# jarvis_mini.net
KiCad netlist of a schematic drawn in Altium Designer
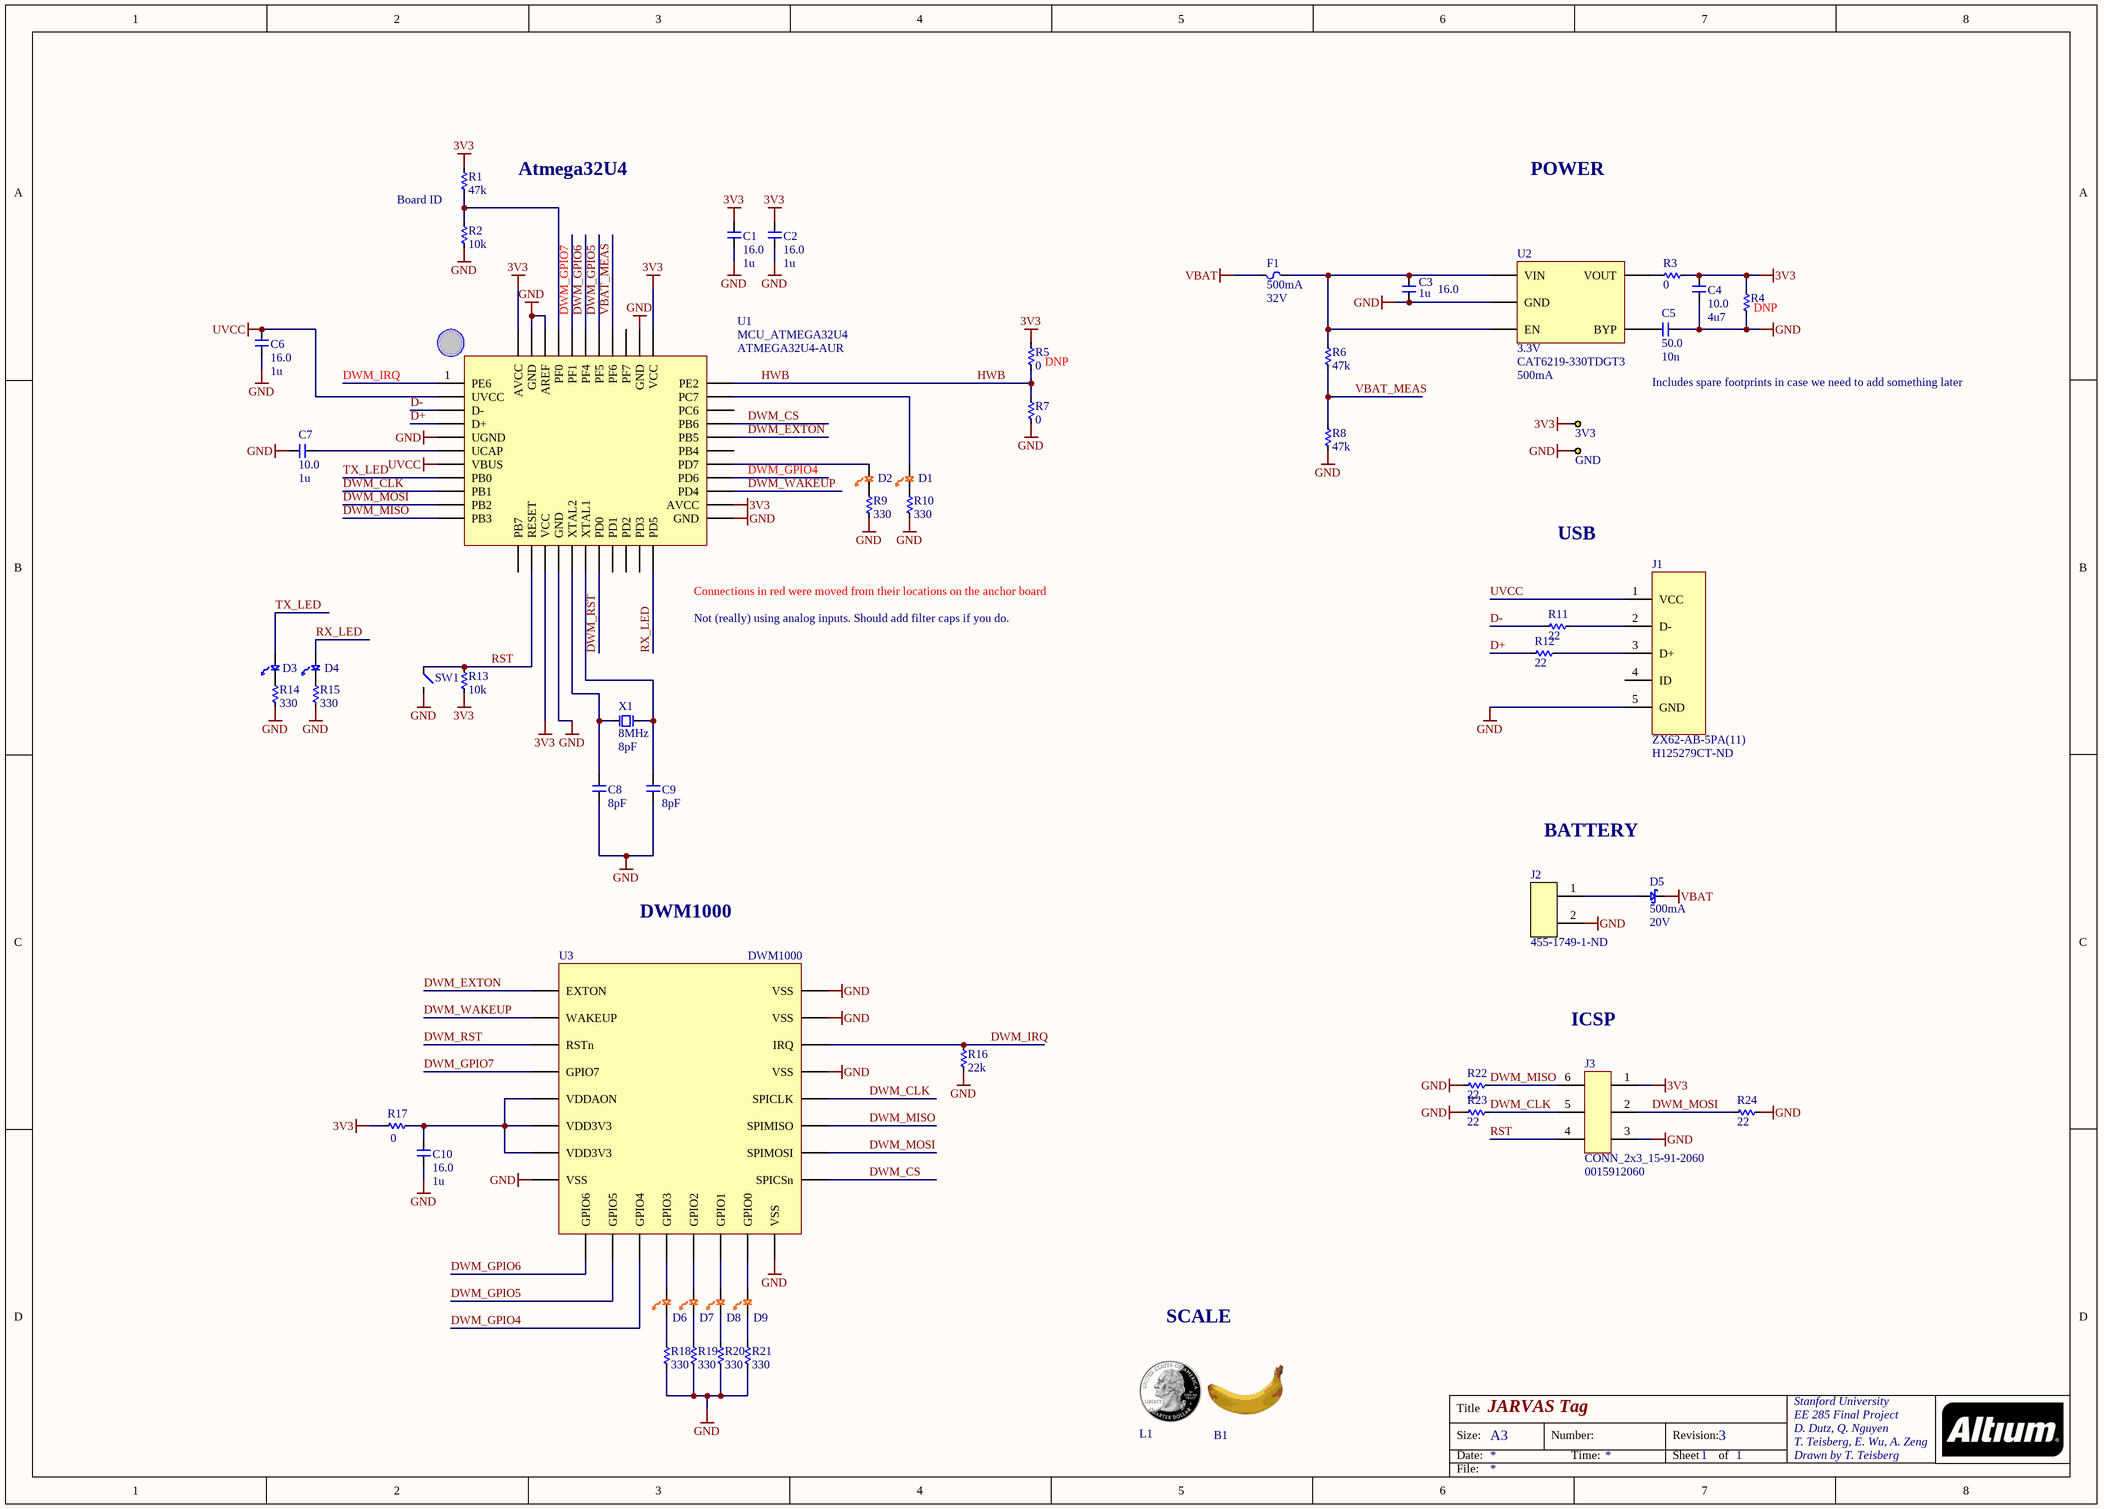
[diagram p0: jarvis_mini.SchDoc]

(export (version "E")
  (design (tool "Eeschema 10.0.6"))
  (components
    (comp (ref "3V3")
      (value "TEST_KEYSTONE5015")
      (footprint "TP_KEYSTONE_5015")
      (description "PC TEST POINT MINIATURE SMT")
      (fields
        (field (name "MANUFACTURER") "Keystone Electronics")
        (field (name "MANUFACTURER PART NUMBER") "5015")
      )
      (libsource (lib "SSI") (part "TEST_KEYSTONE5015"))
    )
    (comp (ref "B1")
      (value "Banananannaa!")
      (footprint "BANANA_OPEN")
      (description "Banana for scale")
      (fields (field (name "MANUFACTURER") "Dole") (field (name "MANUFACTURER PART NUMBER") "B-0000001"))
      (libsource (lib "SSI") (part "BANANA"))
    )
    (comp (ref "C1")
      (value "__template_cap")
      (footprint "C0603")
      (fields
        (field (name "VOLTAGE") "16.0")
        (field (name "HUMAN_VALUE") "1u")
        (field (name "TOLERANCE") "10%")
      )
      (libsource (lib "sscp") (part "__template_cap"))
    )
    (comp (ref "C2")
      (value "__template_cap")
      (footprint "C0603")
      (fields
        (field (name "VOLTAGE") "16.0")
        (field (name "HUMAN_VALUE") "1u")
        (field (name "TOLERANCE") "10%")
      )
      (libsource (lib "sscp") (part "__template_cap"))
    )
    (comp (ref "C3")
      (value "__template_cap")
      (footprint "C0603")
      (fields
        (field (name "VOLTAGE") "16.0")
        (field (name "HUMAN_VALUE") "1u")
        (field (name "TOLERANCE") "10%")
      )
      (libsource (lib "sscp") (part "__template_cap"))
    )
    (comp (ref "C4")
      (value "__template_cap")
      (footprint "C0603")
      (fields
        (field (name "VOLTAGE") "10.0")
        (field (name "HUMAN_VALUE") "4u7")
        (field (name "TOLERANCE") "10%")
      )
      (libsource (lib "sscp") (part "__template_cap"))
    )
    (comp (ref "C5")
      (value "__template_cap")
      (footprint "C0603")
      (fields
        (field (name "VOLTAGE") "50.0")
        (field (name "HUMAN_VALUE") "10n")
        (field (name "TOLERANCE") "5%")
      )
      (libsource (lib "sscp") (part "__template_cap"))
    )
    (comp (ref "C6")
      (value "__template_cap")
      (footprint "C0603")
      (fields
        (field (name "VOLTAGE") "16.0")
        (field (name "HUMAN_VALUE") "1u")
        (field (name "TOLERANCE") "10%")
      )
      (libsource (lib "sscp") (part "__template_cap"))
    )
    (comp (ref "C7")
      (value "__template_cap")
      (footprint "C0603")
      (fields
        (field (name "VOLTAGE") "10.0")
        (field (name "HUMAN_VALUE") "1u")
        (field (name "TOLERANCE") "10%")
      )
      (libsource (lib "sscp") (part "__template_cap"))
    )
    (comp (ref "C8")
      (value "CAP_CER_8PF_100V")
      (footprint "C0603")
      (fields
        (field (name "MANUFACTURER") "AVX Corporation")
        (field (name "MANUFACTURER PART NUMBER") "06031A8R0CAT2A")
        (field (name "TOLERANCE") "±0.25pF")
        (field (name "CAPACITANCE") "8pF")
      )
      (libsource (lib "SSI") (part "CAP_CER_8PF_100V"))
    )
    (comp (ref "C9")
      (value "CAP_CER_8PF_100V")
      (footprint "C0603")
      (fields
        (field (name "MANUFACTURER") "AVX Corporation")
        (field (name "MANUFACTURER PART NUMBER") "06031A8R0CAT2A")
        (field (name "TOLERANCE") "±0.25pF")
        (field (name "CAPACITANCE") "8pF")
      )
      (libsource (lib "SSI") (part "CAP_CER_8PF_100V"))
    )
    (comp (ref "C10")
      (value "__template_cap")
      (footprint "C0603")
      (fields
        (field (name "VOLTAGE") "16.0")
        (field (name "HUMAN_VALUE") "1u")
        (field (name "TOLERANCE") "10%")
      )
      (libsource (lib "sscp") (part "__template_cap"))
    )
    (comp (ref "D1")
      (value "LED")
      (footprint "LED_0603P_ORANGE")
      (description "Orange 605nm LED Indication - Discrete 2V 0603 (1608 Metric)")
      (fields
        (field (name "MANUFACTURER") "Lite-On Inc.")
        (field (name "MANUFACTURER PART NUMBER") "LTST-C190KFKT")
      )
      (libsource (lib "SSI") (part "LED_LTST-C190KFKT_ORANGE"))
    )
    (comp (ref "D2")
      (value "LED")
      (footprint "LED_0603P_ORANGE")
      (description "Orange 605nm LED Indication - Discrete 2V 0603 (1608 Metric)")
      (fields
        (field (name "MANUFACTURER") "Lite-On Inc.")
        (field (name "MANUFACTURER PART NUMBER") "LTST-C190KFKT")
      )
      (libsource (lib "SSI") (part "LED_LTST-C190KFKT_ORANGE"))
    )
    (comp (ref "D3")
      (value "LED_LBQ39G_BLUE")
      (footprint "LED_0603P_BLUE")
      (description "Blue 470nm LED Indication - Discrete 2.85V 0603 (1608 Metric)")
      (fields
        (field (name "MANUFACTURER") "OSRAM Opto Semiconductors Inc.")
        (field (name "MANUFACTURER PART NUMBER") "LB Q39G-L2OO-35-1")
      )
      (libsource (lib "SSI") (part "LED_LBQ39G_BLUE"))
    )
    (comp (ref "D4")
      (value "LED_LBQ39G_BLUE")
      (footprint "LED_0603P_BLUE")
      (description "Blue 470nm LED Indication - Discrete 2.85V 0603 (1608 Metric)")
      (fields
        (field (name "MANUFACTURER") "OSRAM Opto Semiconductors Inc.")
        (field (name "MANUFACTURER PART NUMBER") "LB Q39G-L2OO-35-1")
      )
      (libsource (lib "SSI") (part "LED_LBQ39G_BLUE"))
    )
    (comp (ref "D5")
      (value "SCHOTTKY_MBR0520L")
      (footprint "SOD123")
      (description "DIODE SCHOTTKY 0.5A 20V SOD-123")
      (fields
        (field (name "MANUFACTURER") "Fairchild Semiconductor")
        (field (name "MANUFACTURER PART NUMBER") "MBR0520L")
        (field (name "CURRENT - AVERAGE RECTIFIED (IO)") "500mA")
        (field (name "VOLTAGE - DC REVERSE (VR) (MAX)") "20V")
      )
      (libsource (lib "SSI") (part "SCHOTTKY_MBR0520L"))
    )
    (comp (ref "D6")
      (value "LED")
      (footprint "LED0603")
      (description "Orange 605nm LED Indication - Discrete 2V 0603 (1608 Metric)")
      (fields
        (field (name "MANUFACTURER") "Lite-On Inc.")
        (field (name "MANUFACTURER PART NUMBER") "LTST-C190KFKT")
      )
      (libsource (lib "ee285") (part "LED_LTST-C190KFKT_ORANGE"))
    )
    (comp (ref "D7")
      (value "LED")
      (footprint "LED0603")
      (description "Orange 605nm LED Indication - Discrete 2V 0603 (1608 Metric)")
      (fields
        (field (name "MANUFACTURER") "Lite-On Inc.")
        (field (name "MANUFACTURER PART NUMBER") "LTST-C190KFKT")
      )
      (libsource (lib "ee285") (part "LED_LTST-C190KFKT_ORANGE"))
    )
    (comp (ref "D8")
      (value "LED")
      (footprint "LED0603")
      (description "Orange 605nm LED Indication - Discrete 2V 0603 (1608 Metric)")
      (fields
        (field (name "MANUFACTURER") "Lite-On Inc.")
        (field (name "MANUFACTURER PART NUMBER") "LTST-C190KFKT")
      )
      (libsource (lib "ee285") (part "LED_LTST-C190KFKT_ORANGE"))
    )
    (comp (ref "D9")
      (value "LED")
      (footprint "LED0603")
      (description "Orange 605nm LED Indication - Discrete 2V 0603 (1608 Metric)")
      (fields
        (field (name "MANUFACTURER") "Lite-On Inc.")
        (field (name "MANUFACTURER PART NUMBER") "LTST-C190KFKT")
      )
      (libsource (lib "ee285") (part "LED_LTST-C190KFKT_ORANGE"))
    )
    (comp (ref "F1")
      (value "FAST_MFU0805.50CT-ND")
      (footprint "R0805")
      (description "FUSE .50A 0805 VFAST SMD")
      (fields
        (field (name "MANUFACTURER") "Vishay Beyschlag")
        (field (name "MANUFACTURER PART NUMBER") "MFU0805FF00500P100")
        (field (name "CURRENT RATING") "500mA")
        (field (name "VOLTAGE RATING - DC") "32V")
      )
      (libsource (lib "SSI") (part "FAST_MFU0805.50CT-ND"))
    )
    (comp (ref "GND")
      (value "TEST_KEYSTONE5015")
      (footprint "TP_KEYSTONE_5015")
      (description "PC TEST POINT MINIATURE SMT")
      (fields
        (field (name "MANUFACTURER") "Keystone Electronics")
        (field (name "MANUFACTURER PART NUMBER") "5015")
      )
      (libsource (lib "SSI") (part "TEST_KEYSTONE5015"))
    )
    (comp (ref "J1")
      (value "CONN_USB_MICROAB_SMD_R/A")
      (footprint "HIROSE_ZX62-AB-5PA")
      (description "CONN RCPT MICRO USB AB SMD R/A")
      (fields
        (field (name "MANUFACTURER") "Hirose Electric Co Ltd")
        (field (name "MANUFACTURER PART NUMBER") "ZX62-AB-5PA(11)")
        (field (name "SUPPLIER PART NUMBER 1") "H125279CT-ND")
      )
      (libsource (lib "SSI") (part "CONN_USB_MICROAB_SMD_R/A"))
    )
    (comp (ref "J2")
      (value "CONN JST 2POS SMD")
      (footprint "CONN_JST_PH_SM4_2PIN_RA")
      (description "CONN HEADER PH SIDE 2POS 2MM SMD")
      (fields
        (field (name "MANUFACTURER") "JST Sales America Inc.")
        (field (name "MANUFACTURER PART NUMBER") "S2B-PH-SM4-TB(LF)(SN)")
        (field (name "SUPPLIER PART NUMBER 1") "455-1749-1-ND")
      )
      (libsource (lib "SSI") (part "CONN_JST_2_PH"))
    )
    (comp (ref "J3")
      (value "CONN_2x3_15-91-2060")
      (footprint "MOLEX_15-91-2060")
      (description "CONN HEADER 6POS .100\" VERT TIN")
      (fields
        (field (name "MANUFACTURER") "Molex Inc")
        (field (name "MANUFACTURER PART NUMBER") "0015912060")
      )
      (libsource (lib "SSI") (part "CONN_2x3_15-91-2060"))
    )
    (comp (ref "L1")
      (value "QUARTER")
      (footprint "Quarter")
      (description "Quarter for scale")
      (libsource (lib "SSI") (part "QUARTER"))
    )
    (comp (ref "R1")
      (value "47k")
      (footprint "R0603")
      (description "RES SMD 47K OHM 1% 1/10W 0603")
      (fields
        (field (name "MANUFACTURER PART NUMBER") "CRCW060347K0FKEA")
        (field (name "MANUFACTURER") "Vishay Dale")
      )
      (libsource (lib "resistor") (part "__template_resistor"))
    )
    (comp (ref "R2")
      (value "10k")
      (footprint "R0603")
      (description "RES SMD 10K OHM 1% 1/10W 0603")
      (fields
        (field (name "MANUFACTURER PART NUMBER") "CRCW060310K0FKEA")
        (field (name "MANUFACTURER") "Vishay Dale")
      )
      (libsource (lib "resistor") (part "__template_resistor"))
    )
    (comp (ref "R3")
      (value "0")
      (footprint "R0603")
      (description "RES SMD 0.0 OHM")
      (fields
        (field (name "MANUFACTURER PART NUMBER") "CRCW06030000Z0EA")
        (field (name "MANUFACTURER") "Vishay Dale")
      )
      (libsource (lib "resistor") (part "__template_resistor"))
    )
    (comp (ref "R4")
      (value "__template_resistor")
      (footprint "R0603")
      (description "RES SMD 0.0 OHM")
      (fields
        (field (name "MANUFACTURER PART NUMBER") "CRCW06030000Z0EA")
        (field (name "MANUFACTURER") "Vishay Dale")
        (field (name "DNP") "DNP")
      )
      (libsource (lib "resistor") (part "__template_resistor"))
    )
    (comp (ref "R5")
      (value "0")
      (footprint "R0603")
      (description "RES SMD 0.0 OHM")
      (fields
        (field (name "MANUFACTURER PART NUMBER") "CRCW06030000Z0EA")
        (field (name "MANUFACTURER") "Vishay Dale")
        (field (name "DNP") "DNP")
      )
      (libsource (lib "resistor") (part "__template_resistor"))
    )
    (comp (ref "R6")
      (value "47k")
      (footprint "R0603")
      (description "RES SMD 47K OHM 1% 1/10W 0603")
      (fields
        (field (name "MANUFACTURER PART NUMBER") "CRCW060347K0FKEA")
        (field (name "MANUFACTURER") "Vishay Dale")
      )
      (libsource (lib "resistor") (part "__template_resistor"))
    )
    (comp (ref "R7")
      (value "0")
      (footprint "R0603")
      (description "RES SMD 0.0 OHM")
      (fields
        (field (name "MANUFACTURER PART NUMBER") "CRCW06030000Z0EA")
        (field (name "MANUFACTURER") "Vishay Dale")
      )
      (libsource (lib "resistor") (part "__template_resistor"))
    )
    (comp (ref "R8")
      (value "47k")
      (footprint "R0603")
      (description "RES SMD 47K OHM 1% 1/10W 0603")
      (fields
        (field (name "MANUFACTURER PART NUMBER") "CRCW060347K0FKEA")
        (field (name "MANUFACTURER") "Vishay Dale")
      )
      (libsource (lib "resistor") (part "__template_resistor"))
    )
    (comp (ref "R9")
      (value "330")
      (footprint "R0603")
      (description "RES SMD 330 OHM 1% 1/10W 0603")
      (fields
        (field (name "MANUFACTURER PART NUMBER") "CRCW0603330RFKEA")
        (field (name "MANUFACTURER") "Vishay Dale")
      )
      (libsource (lib "resistor") (part "__template_resistor"))
    )
    (comp (ref "R10")
      (value "330")
      (footprint "R0603")
      (description "RES SMD 330 OHM 1% 1/10W 0603")
      (fields
        (field (name "MANUFACTURER PART NUMBER") "CRCW0603330RFKEA")
        (field (name "MANUFACTURER") "Vishay Dale")
      )
      (libsource (lib "resistor") (part "__template_resistor"))
    )
    (comp (ref "R11")
      (value "22")
      (footprint "R0603")
      (description "RES SMD 22 OHM 1% 1/10W 0603")
      (fields
        (field (name "MANUFACTURER PART NUMBER") "CRCW060322R0FKEA")
        (field (name "MANUFACTURER") "Vishay Dale")
      )
      (libsource (lib "resistor") (part "__template_resistor"))
    )
    (comp (ref "R12")
      (value "22")
      (footprint "R0603")
      (description "RES SMD 22 OHM 1% 1/10W 0603")
      (fields
        (field (name "MANUFACTURER PART NUMBER") "CRCW060322R0FKEA")
        (field (name "MANUFACTURER") "Vishay Dale")
      )
      (libsource (lib "resistor") (part "__template_resistor"))
    )
    (comp (ref "R13")
      (value "10k")
      (footprint "R0603")
      (description "RES SMD 10K OHM 1% 1/10W 0603")
      (fields
        (field (name "MANUFACTURER PART NUMBER") "CRCW060310K0FKEA")
        (field (name "MANUFACTURER") "Vishay Dale")
      )
      (libsource (lib "resistor") (part "__template_resistor"))
    )
    (comp (ref "R14")
      (value "330")
      (footprint "R0603")
      (description "RES SMD 330 OHM 1% 1/10W 0603")
      (fields
        (field (name "MANUFACTURER PART NUMBER") "CRCW0603330RFKEA")
        (field (name "MANUFACTURER") "Vishay Dale")
      )
      (libsource (lib "resistor") (part "__template_resistor"))
    )
    (comp (ref "R15")
      (value "330")
      (footprint "R0603")
      (description "RES SMD 330 OHM 1% 1/10W 0603")
      (fields
        (field (name "MANUFACTURER PART NUMBER") "CRCW0603330RFKEA")
        (field (name "MANUFACTURER") "Vishay Dale")
      )
      (libsource (lib "resistor") (part "__template_resistor"))
    )
    (comp (ref "R16")
      (value "22k")
      (footprint "R0603")
      (description "RES SMD 22K OHM 1% 1/10W 0603")
      (fields
        (field (name "MANUFACTURER PART NUMBER") "CRCW060322K0FKEA")
        (field (name "MANUFACTURER") "Vishay Dale")
      )
      (libsource (lib "resistor") (part "__template_resistor"))
    )
    (comp (ref "R17")
      (value "__template_resistor")
      (footprint "R0603")
      (description "RES SMD 0.0 OHM")
      (fields
        (field (name "MANUFACTURER PART NUMBER") "CRCW06030000Z0EA")
        (field (name "RESISTANCE (MACHINE READABLE)") "0")
        (field (name "MANUFACTURER") "Vishay Dale")
      )
      (libsource (lib "resistor") (part "__template_resistor"))
    )
    (comp (ref "R18")
      (value "330")
      (footprint "R0603")
      (description "RES SMD 330 OHM 1% 1/10W 0603")
      (fields
        (field (name "MANUFACTURER PART NUMBER") "CRCW0603330RFKEA")
        (field (name "MANUFACTURER") "Vishay Dale")
      )
      (libsource (lib "resistor") (part "__template_resistor"))
    )
    (comp (ref "R19")
      (value "330")
      (footprint "R0603")
      (description "RES SMD 330 OHM 1% 1/10W 0603")
      (fields
        (field (name "MANUFACTURER PART NUMBER") "CRCW0603330RFKEA")
        (field (name "MANUFACTURER") "Vishay Dale")
      )
      (libsource (lib "resistor") (part "__template_resistor"))
    )
    (comp (ref "R20")
      (value "330")
      (footprint "R0603")
      (description "RES SMD 330 OHM 1% 1/10W 0603")
      (fields
        (field (name "MANUFACTURER PART NUMBER") "CRCW0603330RFKEA")
        (field (name "MANUFACTURER") "Vishay Dale")
      )
      (libsource (lib "resistor") (part "__template_resistor"))
    )
    (comp (ref "R21")
      (value "330")
      (footprint "R0603")
      (description "RES SMD 330 OHM 1% 1/10W 0603")
      (fields
        (field (name "MANUFACTURER PART NUMBER") "CRCW0603330RFKEA")
        (field (name "MANUFACTURER") "Vishay Dale")
      )
      (libsource (lib "resistor") (part "__template_resistor"))
    )
    (comp (ref "R22")
      (value "22")
      (footprint "R0603")
      (description "RES SMD 22 OHM 1% 1/10W 0603")
      (fields
        (field (name "MANUFACTURER PART NUMBER") "CRCW060322R0FKEA")
        (field (name "MANUFACTURER") "Vishay Dale")
      )
      (libsource (lib "resistor") (part "__template_resistor"))
    )
    (comp (ref "R23")
      (value "22")
      (footprint "R0603")
      (description "RES SMD 22 OHM 1% 1/10W 0603")
      (fields
        (field (name "MANUFACTURER PART NUMBER") "CRCW060322R0FKEA")
        (field (name "MANUFACTURER") "Vishay Dale")
      )
      (libsource (lib "resistor") (part "__template_resistor"))
    )
    (comp (ref "R24")
      (value "22")
      (footprint "R0603")
      (description "RES SMD 22 OHM 1% 1/10W 0603")
      (fields
        (field (name "MANUFACTURER PART NUMBER") "CRCW060322R0FKEA")
        (field (name "MANUFACTURER") "Vishay Dale")
      )
      (libsource (lib "resistor") (part "__template_resistor"))
    )
    (comp (ref "SW1")
      (value "SWITCH_SPST-NO")
      (footprint "SWITCH_B3U-1000P")
      (description "SWITCH TACTILE SPST-NO 0.05A 12V")
      (fields
        (field (name "MANUFACTURER") "Omron Electronics Inc-EMC Div")
        (field (name "MANUFACTURER PART NUMBER") "B3U-1000P")
      )
      (libsource (lib "SSI") (part "SWITCH_SPST-NO"))
    )
    (comp (ref "U1")
      (value "MCU_ATMEGA32U4")
      (footprint "44TQFP10")
      (description "IC MCU 8BIT 32KB FLASH 44TQFP")
      (fields
        (field (name "MANUFACTURER") "Atmel")
        (field (name "MANUFACTURER PART NUMBER") "ATMEGA32U4-AUR")
      )
      (libsource (lib "SSI") (part "MCU_ATMEGA32U4"))
    )
    (comp (ref "U2")
      (value "3.3V LDO")
      (footprint "TSOT-23-5")
      (description "Linear Voltage Regulator IC Positive Fixed 1 Output 3.3V 500mA TSOT-23-5")
      (fields
        (field (name "MANUFACTURER") "ON Semiconductor")
        (field (name "VOLTAGE - OUTPUT") "3.3V")
        (field (name "MANUFACTURER PART NUMBER") "CAT6219-330TDGT3")
        (field (name "CURRENT - OUTPUT") "500mA")
      )
      (libsource (lib "ee285") (part "LDO_CAT6219_3V3"))
    )
    (comp (ref "U3")
      (value "DWM1000")
      (footprint "DW1000")
      (fields (field (name "MANUFACTURER") "Decawave Limited"))
      (libsource (lib "ee285") (part "DWM1000"))
    )
    (comp (ref "X1")
      (value "XTAL_NX5032GA")
      (footprint "XTAL_NDK_NX5032")
      (description "CRYSTAL 8.00 MHZ 8PF SMD")
      (fields
        (field (name "MANUFACTURER") "NDK")
        (field (name "MANUFACTURER PART NUMBER") "NX5032GA 8MHZ AT-W")
        (field (name "FREQUENCY") "8MHz")
        (field (name "LOAD CAPACITANCE") "8pF")
      )
      (libsource (lib "SSI") (part "XTAL_NX5032GA"))
    )
  )
  (nets
    (net (code "1") (name "/D+") (class "Default")
      (node (ref "R12") (pin "1") (pintype "passive"))
      (node (ref "U1") (pin "4") (pinfunction "D+_4") (pintype "passive"))
    )
    (net (code "2") (name "/D-") (class "Default")
      (node (ref "R11") (pin "1") (pintype "passive"))
      (node (ref "U1") (pin "3") (pinfunction "D-_3") (pintype "passive"))
    )
    (net (code "3") (name "/DWM_CLK") (class "Default")
      (node (ref "J3") (pin "5") (pintype "passive"))
      (node (ref "R23") (pin "2") (pintype "passive"))
      (node (ref "U1") (pin "9") (pinfunction "PB1_9") (pintype "passive"))
      (node (ref "U3") (pin "20") (pinfunction "SPICLK_20") (pintype "passive"))
    )
    (net (code "4") (name "/DWM_CS") (class "Default")
      (node (ref "U1") (pin "30") (pinfunction "PB6_30") (pintype "passive"))
      (node (ref "U3") (pin "17") (pinfunction "SPICSn_17") (pintype "passive"))
    )
    (net (code "5") (name "/DWM_EXTON") (class "Default")
      (node (ref "U1") (pin "29") (pinfunction "PB5_29") (pintype "passive"))
      (node (ref "U3") (pin "1") (pinfunction "EXTON_1") (pintype "passive"))
    )
    (net (code "6") (name "/DWM_GPIO4") (class "Default")
      (node (ref "U1") (pin "26") (pinfunction "PD6_26") (pintype "passive"))
      (node (ref "U3") (pin "11") (pinfunction "GPIO4_11") (pintype "passive"))
    )
    (net (code "7") (name "/DWM_GPIO5") (class "Default")
      (node (ref "U1") (pin "38") (pinfunction "PF5_38") (pintype "passive"))
      (node (ref "U3") (pin "10") (pinfunction "GPIO5_10") (pintype "passive"))
    )
    (net (code "8") (name "/DWM_GPIO6") (class "Default")
      (node (ref "U1") (pin "39") (pinfunction "PF4_39") (pintype "passive"))
      (node (ref "U3") (pin "9") (pinfunction "GPIO6_9") (pintype "passive"))
    )
    (net (code "9") (name "/DWM_GPIO7") (class "Default")
      (node (ref "U1") (pin "40") (pinfunction "PF1_40") (pintype "passive"))
      (node (ref "U3") (pin "4") (pinfunction "GPIO7_4") (pintype "passive"))
    )
    (net (code "10") (name "/DWM_IRQ") (class "Default")
      (node (ref "R16") (pin "2") (pintype "passive"))
      (node (ref "U1") (pin "1") (pinfunction "PE6_1") (pintype "passive"))
      (node (ref "U3") (pin "22") (pinfunction "IRQ_22") (pintype "passive"))
    )
    (net (code "11") (name "/DWM_MISO") (class "Default")
      (node (ref "J3") (pin "6") (pintype "passive"))
      (node (ref "R22") (pin "2") (pintype "passive"))
      (node (ref "U1") (pin "11") (pinfunction "PB3_11") (pintype "passive"))
      (node (ref "U3") (pin "19") (pinfunction "SPIMISO_19") (pintype "passive"))
    )
    (net (code "12") (name "/DWM_MOSI") (class "Default")
      (node (ref "J3") (pin "2") (pintype "passive"))
      (node (ref "R24") (pin "1") (pintype "passive"))
      (node (ref "U1") (pin "10") (pinfunction "PB2_10") (pintype "passive"))
      (node (ref "U3") (pin "18") (pinfunction "SPIMOSI_18") (pintype "passive"))
    )
    (net (code "13") (name "/DWM_RST") (class "Default")
      (node (ref "U1") (pin "18") (pinfunction "PD0_18") (pintype "passive"))
      (node (ref "U3") (pin "3") (pinfunction "RSTn_3") (pintype "passive"))
    )
    (net (code "14") (name "/DWM_WAKEUP") (class "Default")
      (node (ref "U1") (pin "25") (pinfunction "PD4_25") (pintype "passive"))
      (node (ref "U3") (pin "2") (pinfunction "WAKEUP_2") (pintype "passive"))
    )
    (net (code "15") (name "/HWB") (class "Default")
      (node (ref "R5") (pin "1") (pintype "passive"))
      (node (ref "R7") (pin "2") (pintype "passive"))
      (node (ref "U1") (pin "33") (pinfunction "PE2_33") (pintype "passive"))
    )
    (net (code "16") (name "/RST") (class "Default")
      (node (ref "J3") (pin "4") (pintype "passive"))
      (node (ref "R13") (pin "2") (pintype "passive"))
      (node (ref "SW1") (pin "1") (pintype "passive"))
      (node (ref "U1") (pin "13") (pinfunction "RESET_13") (pintype "passive"))
    )
    (net (code "17") (name "/RX_LED") (class "Default")
      (node (ref "D4") (pin "2") (pintype "passive"))
      (node (ref "U1") (pin "22") (pinfunction "PD5_22") (pintype "passive"))
    )
    (net (code "18") (name "/TX_LED") (class "Default")
      (node (ref "D3") (pin "2") (pintype "passive"))
      (node (ref "U1") (pin "8") (pinfunction "PB0_8") (pintype "passive"))
    )
    (net (code "19") (name "/VBAT_MEAS") (class "Default")
      (node (ref "R6") (pin "1") (pintype "passive"))
      (node (ref "R8") (pin "2") (pintype "passive"))
      (node (ref "U1") (pin "37") (pinfunction "PF6_37") (pintype "passive"))
    )
    (net (code "20") (name "3V3") (class "Default")
      (node (ref "3V3") (pin "1") (pintype "passive"))
      (node (ref "C1") (pin "1") (pintype "passive"))
      (node (ref "C2") (pin "1") (pintype "passive"))
      (node (ref "C4") (pin "2") (pintype "passive"))
      (node (ref "J3") (pin "1") (pintype "passive"))
      (node (ref "R1") (pin "2") (pintype "passive"))
      (node (ref "R13") (pin "1") (pintype "passive"))
      (node (ref "R17") (pin "1") (pintype "passive"))
      (node (ref "R3") (pin "2") (pintype "passive"))
      (node (ref "R4") (pin "2") (pintype "passive"))
      (node (ref "R5") (pin "2") (pintype "passive"))
      (node (ref "U1") (pin "14") (pinfunction "VCC_14") (pintype "passive"))
      (node (ref "U1") (pin "24") (pinfunction "AVCC_24") (pintype "passive"))
      (node (ref "U1") (pin "34") (pinfunction "VCC_34") (pintype "passive"))
      (node (ref "U1") (pin "44") (pinfunction "AVCC_44") (pintype "passive"))
    )
    (net (code "21") (name "GND") (class "Default")
      (node (ref "C1") (pin "2") (pintype "passive"))
      (node (ref "C10") (pin "2") (pintype "passive"))
      (node (ref "C2") (pin "2") (pintype "passive"))
      (node (ref "C3") (pin "1") (pintype "passive"))
      (node (ref "C4") (pin "1") (pintype "passive"))
      (node (ref "C5") (pin "2") (pintype "passive"))
      (node (ref "C6") (pin "2") (pintype "passive"))
      (node (ref "C7") (pin "1") (pintype "passive"))
      (node (ref "C8") (pin "2") (pintype "passive"))
      (node (ref "C9") (pin "2") (pintype "passive"))
      (node (ref "GND") (pin "1") (pintype "passive"))
      (node (ref "J1") (pin "5") (pinfunction "GND_5") (pintype "passive"))
      (node (ref "J2") (pin "2") (pinfunction "2_2") (pintype "passive"))
      (node (ref "J3") (pin "3") (pintype "passive"))
      (node (ref "R10") (pin "1") (pintype "passive"))
      (node (ref "R14") (pin "1") (pintype "passive"))
      (node (ref "R15") (pin "1") (pintype "passive"))
      (node (ref "R16") (pin "1") (pintype "passive"))
      (node (ref "R18") (pin "1") (pintype "passive"))
      (node (ref "R19") (pin "1") (pintype "passive"))
      (node (ref "R2") (pin "1") (pintype "passive"))
      (node (ref "R20") (pin "1") (pintype "passive"))
      (node (ref "R21") (pin "1") (pintype "passive"))
      (node (ref "R22") (pin "1") (pintype "passive"))
      (node (ref "R23") (pin "1") (pintype "passive"))
      (node (ref "R24") (pin "2") (pintype "passive"))
      (node (ref "R4") (pin "1") (pintype "passive"))
      (node (ref "R7") (pin "1") (pintype "passive"))
      (node (ref "R8") (pin "1") (pintype "passive"))
      (node (ref "R9") (pin "1") (pintype "passive"))
      (node (ref "SW1") (pin "2") (pintype "passive"))
      (node (ref "U1") (pin "15") (pinfunction "GND_15") (pintype "passive"))
      (node (ref "U1") (pin "23") (pinfunction "GND_23") (pintype "passive"))
      (node (ref "U1") (pin "35") (pinfunction "GND_35") (pintype "passive"))
      (node (ref "U1") (pin "42") (pinfunction "AREF_42") (pintype "passive"))
      (node (ref "U1") (pin "43") (pinfunction "GND_43") (pintype "passive"))
      (node (ref "U1") (pin "5") (pinfunction "UGND_5") (pintype "passive"))
      (node (ref "U2") (pin "2") (pinfunction "GND_2") (pintype "passive"))
      (node (ref "U3") (pin "16") (pinfunction "VSS_16") (pintype "passive"))
      (node (ref "U3") (pin "21") (pinfunction "VSS_21") (pintype "passive"))
      (node (ref "U3") (pin "23") (pinfunction "VSS_23") (pintype "passive"))
      (node (ref "U3") (pin "24") (pinfunction "VSS_24") (pintype "passive"))
      (node (ref "U3") (pin "8") (pinfunction "VSS_8") (pintype "passive"))
    )
    (net (code "22") (name "Net-(D1-PadK)") (class "Default")
      (node (ref "D1") (pin "K") (pintype "passive"))
      (node (ref "R10") (pin "2") (pintype "passive"))
    )
    (net (code "23") (name "Net-(D2-PadK)") (class "Default")
      (node (ref "D2") (pin "K") (pintype "passive"))
      (node (ref "R9") (pin "2") (pintype "passive"))
    )
    (net (code "24") (name "Net-(D3-Pad1)") (class "Default")
      (node (ref "D3") (pin "1") (pintype "passive"))
      (node (ref "R14") (pin "2") (pintype "passive"))
    )
    (net (code "25") (name "Net-(D4-Pad1)") (class "Default")
      (node (ref "D4") (pin "1") (pintype "passive"))
      (node (ref "R15") (pin "2") (pintype "passive"))
    )
    (net (code "26") (name "Net-(D5-Pad1)") (class "Default")
      (node (ref "D5") (pin "1") (pintype "passive"))
      (node (ref "J2") (pin "1") (pinfunction "1_1") (pintype "passive"))
    )
    (net (code "27") (name "Net-(D6-PadK)") (class "Default")
      (node (ref "D6") (pin "K") (pintype "passive"))
      (node (ref "R18") (pin "2") (pintype "passive"))
    )
    (net (code "28") (name "Net-(D7-PadK)") (class "Default")
      (node (ref "D7") (pin "K") (pintype "passive"))
      (node (ref "R19") (pin "2") (pintype "passive"))
    )
    (net (code "29") (name "Net-(D8-PadK)") (class "Default")
      (node (ref "D8") (pin "K") (pintype "passive"))
      (node (ref "R20") (pin "2") (pintype "passive"))
    )
    (net (code "30") (name "Net-(D9-PadK)") (class "Default")
      (node (ref "D9") (pin "K") (pintype "passive"))
      (node (ref "R21") (pin "2") (pintype "passive"))
    )
    (net (code "31") (name "Net-(J1-D+)") (class "Default")
      (node (ref "J1") (pin "3") (pinfunction "D+_3") (pintype "passive"))
      (node (ref "R12") (pin "2") (pintype "passive"))
    )
    (net (code "32") (name "Net-(J1-D-)") (class "Default")
      (node (ref "J1") (pin "2") (pinfunction "D-_2") (pintype "passive"))
      (node (ref "R11") (pin "2") (pintype "passive"))
    )
    (net (code "33") (name "Net-(U1-PC7)") (class "Default")
      (node (ref "D1") (pin "A") (pintype "passive"))
      (node (ref "U1") (pin "32") (pinfunction "PC7_32") (pintype "passive"))
    )
    (net (code "34") (name "Net-(U1-PD7)") (class "Default")
      (node (ref "D2") (pin "A") (pintype "passive"))
      (node (ref "U1") (pin "27") (pinfunction "PD7_27") (pintype "passive"))
    )
    (net (code "35") (name "Net-(U1-PF0)") (class "Default")
      (node (ref "R1") (pin "1") (pintype "passive"))
      (node (ref "R2") (pin "2") (pintype "passive"))
      (node (ref "U1") (pin "41") (pinfunction "PF0_41") (pintype "passive"))
    )
    (net (code "36") (name "Net-(U1-UCAP)") (class "Default")
      (node (ref "C7") (pin "2") (pintype "passive"))
      (node (ref "U1") (pin "6") (pinfunction "UCAP_6") (pintype "passive"))
    )
    (net (code "37") (name "Net-(U1-XTAL1)") (class "Default")
      (node (ref "C9") (pin "1") (pintype "passive"))
      (node (ref "U1") (pin "17") (pinfunction "XTAL1_17") (pintype "passive"))
      (node (ref "X1") (pin "1") (pinfunction "1_1") (pintype "passive"))
    )
    (net (code "38") (name "Net-(U1-XTAL2)") (class "Default")
      (node (ref "C8") (pin "1") (pintype "passive"))
      (node (ref "U1") (pin "16") (pinfunction "XTAL2_16") (pintype "passive"))
      (node (ref "X1") (pin "2") (pinfunction "2_2") (pintype "passive"))
    )
    (net (code "39") (name "Net-(U2-BYP)") (class "Default")
      (node (ref "C5") (pin "1") (pintype "passive"))
      (node (ref "U2") (pin "4") (pinfunction "BYP_4") (pintype "passive"))
    )
    (net (code "40") (name "Net-(U2-EN)") (class "Default")
      (node (ref "C3") (pin "2") (pintype "passive"))
      (node (ref "F1") (pin "2") (pintype "passive"))
      (node (ref "R6") (pin "2") (pintype "passive"))
      (node (ref "U2") (pin "1") (pinfunction "VIN_1") (pintype "passive"))
      (node (ref "U2") (pin "3") (pinfunction "EN_3") (pintype "passive"))
    )
    (net (code "41") (name "Net-(U2-VOUT)") (class "Default")
      (node (ref "R3") (pin "1") (pintype "passive"))
      (node (ref "U2") (pin "5") (pinfunction "VOUT_5") (pintype "passive"))
    )
    (net (code "42") (name "Net-(U3-GPIO0)") (class "Default")
      (node (ref "D9") (pin "A") (pintype "passive"))
      (node (ref "U3") (pin "15") (pinfunction "GPIO0_15") (pintype "passive"))
    )
    (net (code "43") (name "Net-(U3-GPIO1)") (class "Default")
      (node (ref "D8") (pin "A") (pintype "passive"))
      (node (ref "U3") (pin "14") (pinfunction "GPIO1_14") (pintype "passive"))
    )
    (net (code "44") (name "Net-(U3-GPIO2)") (class "Default")
      (node (ref "D7") (pin "A") (pintype "passive"))
      (node (ref "U3") (pin "13") (pinfunction "GPIO2_13") (pintype "passive"))
    )
    (net (code "45") (name "Net-(U3-GPIO3)") (class "Default")
      (node (ref "D6") (pin "A") (pintype "passive"))
      (node (ref "U3") (pin "12") (pinfunction "GPIO3_12") (pintype "passive"))
    )
    (net (code "46") (name "Net-(U3-VDDAON)") (class "Default")
      (node (ref "C10") (pin "1") (pintype "passive"))
      (node (ref "R17") (pin "2") (pintype "passive"))
      (node (ref "U3") (pin "5") (pinfunction "VDDAON_5") (pintype "passive"))
      (node (ref "U3") (pin "6") (pinfunction "VDD3V3_6") (pintype "passive"))
      (node (ref "U3") (pin "7") (pinfunction "VDD3V3_7") (pintype "passive"))
    )
    (net (code "47") (name "UVCC") (class "Default")
      (node (ref "C6") (pin "1") (pintype "passive"))
      (node (ref "J1") (pin "1") (pinfunction "VCC_1") (pintype "passive"))
      (node (ref "U1") (pin "2") (pinfunction "UVCC_2") (pintype "passive"))
      (node (ref "U1") (pin "7") (pinfunction "VBUS_7") (pintype "passive"))
    )
    (net (code "48") (name "VBAT") (class "Default")
      (node (ref "D5") (pin "2") (pintype "passive"))
      (node (ref "F1") (pin "1") (pintype "passive"))
    )
    (net (code "49") (name "unconnected-(J1-ID-Pad4)") (class "Default")
      (node (ref "J1") (pin "4") (pinfunction "ID_4") (pintype "passive"))
    )
    (net (code "50") (name "unconnected-(U1-PB4-Pad28)") (class "Default")
      (node (ref "U1") (pin "28") (pinfunction "PB4_28") (pintype "passive"))
    )
    (net (code "51") (name "unconnected-(U1-PB7-Pad12)") (class "Default")
      (node (ref "U1") (pin "12") (pinfunction "PB7_12") (pintype "passive"))
    )
    (net (code "52") (name "unconnected-(U1-PC6-Pad31)") (class "Default")
      (node (ref "U1") (pin "31") (pinfunction "PC6_31") (pintype "passive"))
    )
    (net (code "53") (name "unconnected-(U1-PD1-Pad19)") (class "Default")
      (node (ref "U1") (pin "19") (pinfunction "PD1_19") (pintype "passive"))
    )
    (net (code "54") (name "unconnected-(U1-PD2-Pad20)") (class "Default")
      (node (ref "U1") (pin "20") (pinfunction "PD2_20") (pintype "passive"))
    )
    (net (code "55") (name "unconnected-(U1-PD3-Pad21)") (class "Default")
      (node (ref "U1") (pin "21") (pinfunction "PD3_21") (pintype "passive"))
    )
    (net (code "56") (name "unconnected-(U1-PF7-Pad36)") (class "Default")
      (node (ref "U1") (pin "36") (pinfunction "PF7_36") (pintype "passive"))
    )
  )
)
